# input1.net
KiCad netlist of a schematic drawn in Altium Designer
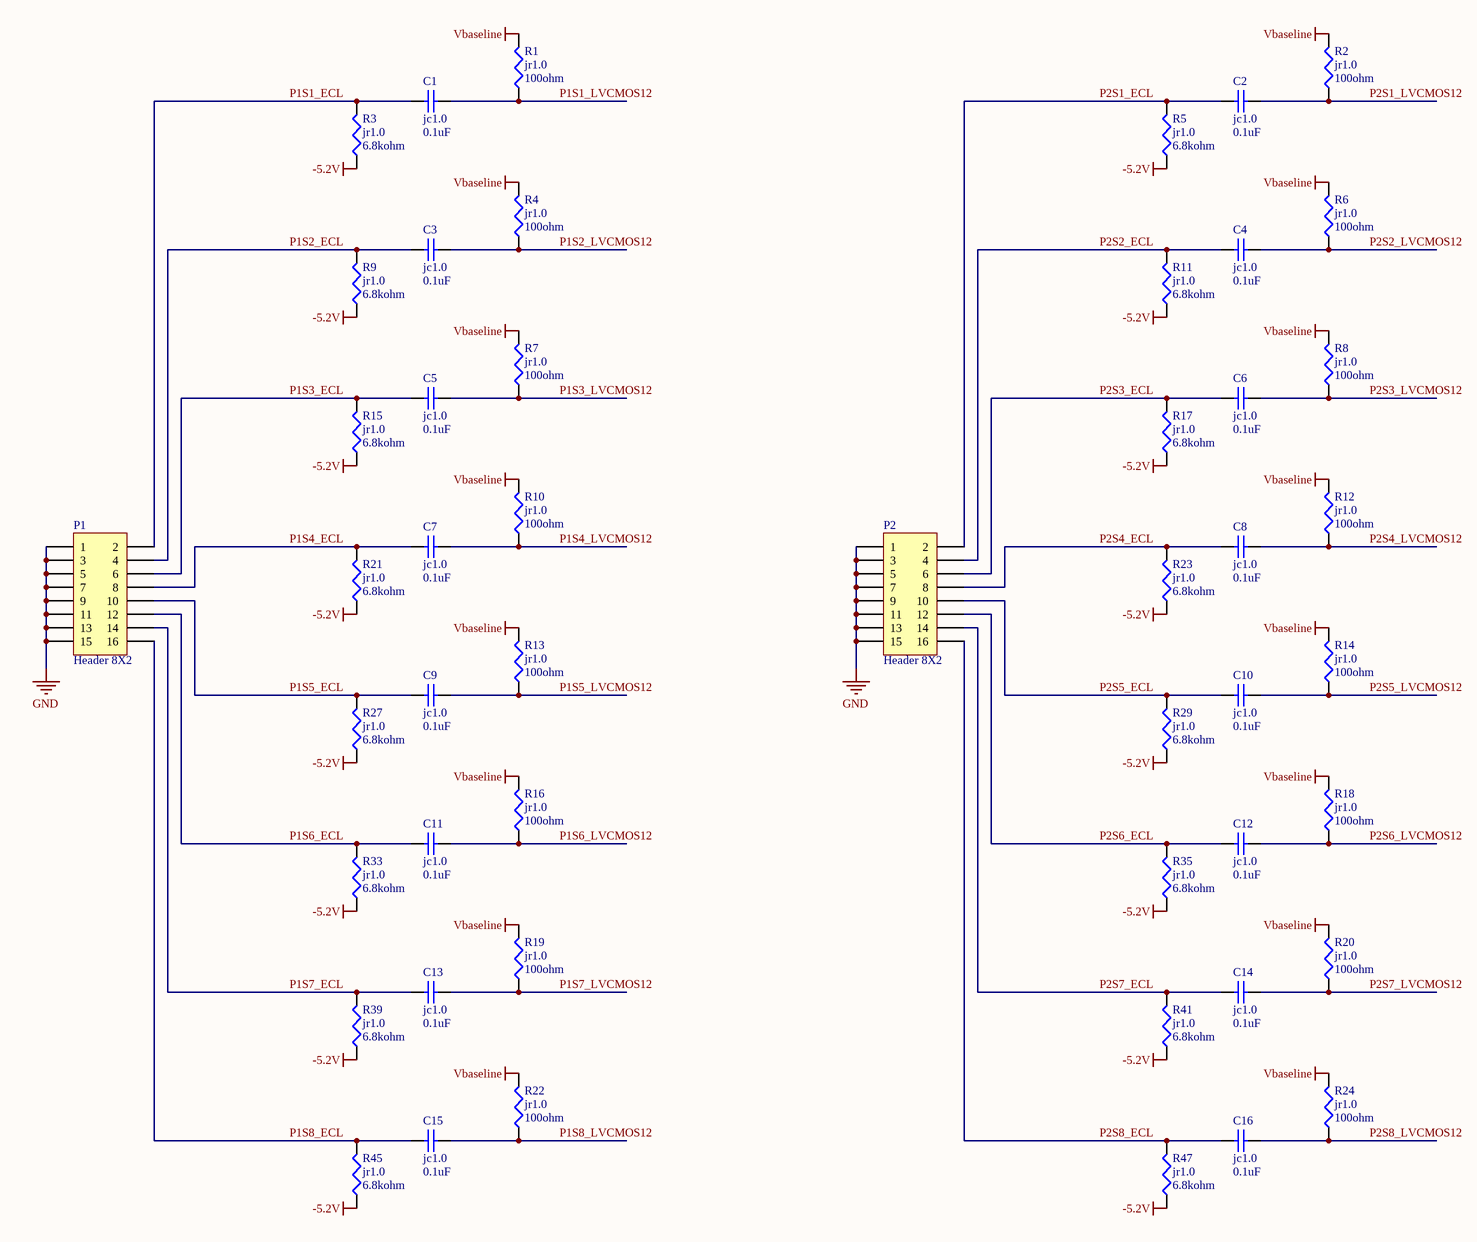
[diagram p0: input1.SchDoc]

(export (version "E")
  (design (tool "Eeschema 10.0.6"))
  (components
    (comp (ref "C1")
      (value "jc1.0")
      (footprint "0402")
      (description "Capacitor")
      (fields (field (name "ALTIUM_VALUE") "0.1uF") (field (name "PUBLISHER") "Altium Limited"))
      (libsource (lib "LIB01DXP2006SchLib") (part "Cap"))
    )
    (comp (ref "C2")
      (value "jc1.0")
      (footprint "0402")
      (description "Capacitor")
      (fields (field (name "ALTIUM_VALUE") "0.1uF") (field (name "PUBLISHER") "Altium Limited"))
      (libsource (lib "LIB01DXP2006SchLib") (part "Cap"))
    )
    (comp (ref "C3")
      (value "jc1.0")
      (footprint "0402")
      (description "Capacitor")
      (fields (field (name "ALTIUM_VALUE") "0.1uF") (field (name "PUBLISHER") "Altium Limited"))
      (libsource (lib "LIB01DXP2006SchLib") (part "Cap"))
    )
    (comp (ref "C4")
      (value "jc1.0")
      (footprint "0402")
      (description "Capacitor")
      (fields (field (name "ALTIUM_VALUE") "0.1uF") (field (name "PUBLISHER") "Altium Limited"))
      (libsource (lib "LIB01DXP2006SchLib") (part "Cap"))
    )
    (comp (ref "C5")
      (value "jc1.0")
      (footprint "0402")
      (description "Capacitor")
      (fields (field (name "ALTIUM_VALUE") "0.1uF") (field (name "PUBLISHER") "Altium Limited"))
      (libsource (lib "LIB01DXP2006SchLib") (part "Cap"))
    )
    (comp (ref "C6")
      (value "jc1.0")
      (footprint "0402")
      (description "Capacitor")
      (fields (field (name "ALTIUM_VALUE") "0.1uF") (field (name "PUBLISHER") "Altium Limited"))
      (libsource (lib "LIB01DXP2006SchLib") (part "Cap"))
    )
    (comp (ref "C7")
      (value "jc1.0")
      (footprint "0402")
      (description "Capacitor")
      (fields (field (name "ALTIUM_VALUE") "0.1uF") (field (name "PUBLISHER") "Altium Limited"))
      (libsource (lib "LIB01DXP2006SchLib") (part "Cap"))
    )
    (comp (ref "C8")
      (value "jc1.0")
      (footprint "0402")
      (description "Capacitor")
      (fields (field (name "ALTIUM_VALUE") "0.1uF") (field (name "PUBLISHER") "Altium Limited"))
      (libsource (lib "LIB01DXP2006SchLib") (part "Cap"))
    )
    (comp (ref "C9")
      (value "jc1.0")
      (footprint "0402")
      (description "Capacitor")
      (fields (field (name "ALTIUM_VALUE") "0.1uF") (field (name "PUBLISHER") "Altium Limited"))
      (libsource (lib "LIB01DXP2006SchLib") (part "Cap"))
    )
    (comp (ref "C10")
      (value "jc1.0")
      (footprint "0402")
      (description "Capacitor")
      (fields (field (name "ALTIUM_VALUE") "0.1uF") (field (name "PUBLISHER") "Altium Limited"))
      (libsource (lib "LIB01DXP2006SchLib") (part "Cap"))
    )
    (comp (ref "C11")
      (value "jc1.0")
      (footprint "0402")
      (description "Capacitor")
      (fields (field (name "ALTIUM_VALUE") "0.1uF") (field (name "PUBLISHER") "Altium Limited"))
      (libsource (lib "LIB01DXP2006SchLib") (part "Cap"))
    )
    (comp (ref "C12")
      (value "jc1.0")
      (footprint "0402")
      (description "Capacitor")
      (fields (field (name "ALTIUM_VALUE") "0.1uF") (field (name "PUBLISHER") "Altium Limited"))
      (libsource (lib "LIB01DXP2006SchLib") (part "Cap"))
    )
    (comp (ref "C13")
      (value "jc1.0")
      (footprint "0402")
      (description "Capacitor")
      (fields (field (name "ALTIUM_VALUE") "0.1uF") (field (name "PUBLISHER") "Altium Limited"))
      (libsource (lib "LIB01DXP2006SchLib") (part "Cap"))
    )
    (comp (ref "C14")
      (value "jc1.0")
      (footprint "0402")
      (description "Capacitor")
      (fields (field (name "ALTIUM_VALUE") "0.1uF") (field (name "PUBLISHER") "Altium Limited"))
      (libsource (lib "LIB01DXP2006SchLib") (part "Cap"))
    )
    (comp (ref "C15")
      (value "jc1.0")
      (footprint "0402")
      (description "Capacitor")
      (fields (field (name "ALTIUM_VALUE") "0.1uF") (field (name "PUBLISHER") "Altium Limited"))
      (libsource (lib "LIB01DXP2006SchLib") (part "Cap"))
    )
    (comp (ref "C16")
      (value "jc1.0")
      (footprint "0402")
      (description "Capacitor")
      (fields (field (name "ALTIUM_VALUE") "0.1uF") (field (name "PUBLISHER") "Altium Limited"))
      (libsource (lib "LIB01DXP2006SchLib") (part "Cap"))
    )
    (comp (ref "P1")
      (value "Header 8X2")
      (footprint "HDR2X8")
      (description "Header, 8-Pin, Dual row")
      (fields (field (name "PUBLISHER") "Altium Limited"))
      (libsource (lib "Miscellaneous Connectors") (part "Header 8X2"))
    )
    (comp (ref "P2")
      (value "Header 8X2")
      (footprint "HDR2X8")
      (description "Header, 8-Pin, Dual row")
      (fields (field (name "PUBLISHER") "Altium Limited"))
      (libsource (lib "Miscellaneous Connectors") (part "Header 8X2"))
    )
    (comp (ref "R1")
      (value "jr1.0")
      (footprint "0402")
      (description "Resistor")
      (fields (field (name "ALTIUM_VALUE") "100ohm") (field (name "PUBLISHER") "Altium Limited"))
      (libsource (lib "LIB01DXP2006SchLib") (part "Res"))
    )
    (comp (ref "R2")
      (value "jr1.0")
      (footprint "0402")
      (description "Resistor")
      (fields (field (name "ALTIUM_VALUE") "100ohm") (field (name "PUBLISHER") "Altium Limited"))
      (libsource (lib "LIB01DXP2006SchLib") (part "Res"))
    )
    (comp (ref "R3")
      (value "jr1.0")
      (footprint "0402")
      (description "Resistor")
      (fields (field (name "ALTIUM_VALUE") "6.8kohm") (field (name "PUBLISHER") "Altium Limited"))
      (libsource (lib "LIB01DXP2006SchLib") (part "Res"))
    )
    (comp (ref "R4")
      (value "jr1.0")
      (footprint "0402")
      (description "Resistor")
      (fields (field (name "ALTIUM_VALUE") "100ohm") (field (name "PUBLISHER") "Altium Limited"))
      (libsource (lib "LIB01DXP2006SchLib") (part "Res"))
    )
    (comp (ref "R5")
      (value "jr1.0")
      (footprint "0402")
      (description "Resistor")
      (fields (field (name "ALTIUM_VALUE") "6.8kohm") (field (name "PUBLISHER") "Altium Limited"))
      (libsource (lib "LIB01DXP2006SchLib") (part "Res"))
    )
    (comp (ref "R6")
      (value "jr1.0")
      (footprint "0402")
      (description "Resistor")
      (fields (field (name "ALTIUM_VALUE") "100ohm") (field (name "PUBLISHER") "Altium Limited"))
      (libsource (lib "LIB01DXP2006SchLib") (part "Res"))
    )
    (comp (ref "R7")
      (value "jr1.0")
      (footprint "0402")
      (description "Resistor")
      (fields (field (name "ALTIUM_VALUE") "100ohm") (field (name "PUBLISHER") "Altium Limited"))
      (libsource (lib "LIB01DXP2006SchLib") (part "Res"))
    )
    (comp (ref "R8")
      (value "jr1.0")
      (footprint "0402")
      (description "Resistor")
      (fields (field (name "ALTIUM_VALUE") "100ohm") (field (name "PUBLISHER") "Altium Limited"))
      (libsource (lib "LIB01DXP2006SchLib") (part "Res"))
    )
    (comp (ref "R9")
      (value "jr1.0")
      (footprint "0402")
      (description "Resistor")
      (fields (field (name "ALTIUM_VALUE") "6.8kohm") (field (name "PUBLISHER") "Altium Limited"))
      (libsource (lib "LIB01DXP2006SchLib") (part "Res"))
    )
    (comp (ref "R10")
      (value "jr1.0")
      (footprint "0402")
      (description "Resistor")
      (fields (field (name "ALTIUM_VALUE") "100ohm") (field (name "PUBLISHER") "Altium Limited"))
      (libsource (lib "LIB01DXP2006SchLib") (part "Res"))
    )
    (comp (ref "R11")
      (value "jr1.0")
      (footprint "0402")
      (description "Resistor")
      (fields (field (name "ALTIUM_VALUE") "6.8kohm") (field (name "PUBLISHER") "Altium Limited"))
      (libsource (lib "LIB01DXP2006SchLib") (part "Res"))
    )
    (comp (ref "R12")
      (value "jr1.0")
      (footprint "0402")
      (description "Resistor")
      (fields (field (name "ALTIUM_VALUE") "100ohm") (field (name "PUBLISHER") "Altium Limited"))
      (libsource (lib "LIB01DXP2006SchLib") (part "Res"))
    )
    (comp (ref "R13")
      (value "jr1.0")
      (footprint "0402")
      (description "Resistor")
      (fields (field (name "ALTIUM_VALUE") "100ohm") (field (name "PUBLISHER") "Altium Limited"))
      (libsource (lib "LIB01DXP2006SchLib") (part "Res"))
    )
    (comp (ref "R14")
      (value "jr1.0")
      (footprint "0402")
      (description "Resistor")
      (fields (field (name "ALTIUM_VALUE") "100ohm") (field (name "PUBLISHER") "Altium Limited"))
      (libsource (lib "LIB01DXP2006SchLib") (part "Res"))
    )
    (comp (ref "R15")
      (value "jr1.0")
      (footprint "0402")
      (description "Resistor")
      (fields (field (name "ALTIUM_VALUE") "6.8kohm") (field (name "PUBLISHER") "Altium Limited"))
      (libsource (lib "LIB01DXP2006SchLib") (part "Res"))
    )
    (comp (ref "R16")
      (value "jr1.0")
      (footprint "0402")
      (description "Resistor")
      (fields (field (name "ALTIUM_VALUE") "100ohm") (field (name "PUBLISHER") "Altium Limited"))
      (libsource (lib "LIB01DXP2006SchLib") (part "Res"))
    )
    (comp (ref "R17")
      (value "jr1.0")
      (footprint "0402")
      (description "Resistor")
      (fields (field (name "ALTIUM_VALUE") "6.8kohm") (field (name "PUBLISHER") "Altium Limited"))
      (libsource (lib "LIB01DXP2006SchLib") (part "Res"))
    )
    (comp (ref "R18")
      (value "jr1.0")
      (footprint "0402")
      (description "Resistor")
      (fields (field (name "ALTIUM_VALUE") "100ohm") (field (name "PUBLISHER") "Altium Limited"))
      (libsource (lib "LIB01DXP2006SchLib") (part "Res"))
    )
    (comp (ref "R19")
      (value "jr1.0")
      (footprint "0402")
      (description "Resistor")
      (fields (field (name "ALTIUM_VALUE") "100ohm") (field (name "PUBLISHER") "Altium Limited"))
      (libsource (lib "LIB01DXP2006SchLib") (part "Res"))
    )
    (comp (ref "R20")
      (value "jr1.0")
      (footprint "0402")
      (description "Resistor")
      (fields (field (name "ALTIUM_VALUE") "100ohm") (field (name "PUBLISHER") "Altium Limited"))
      (libsource (lib "LIB01DXP2006SchLib") (part "Res"))
    )
    (comp (ref "R21")
      (value "jr1.0")
      (footprint "0402")
      (description "Resistor")
      (fields (field (name "ALTIUM_VALUE") "6.8kohm") (field (name "PUBLISHER") "Altium Limited"))
      (libsource (lib "LIB01DXP2006SchLib") (part "Res"))
    )
    (comp (ref "R22")
      (value "jr1.0")
      (footprint "0402")
      (description "Resistor")
      (fields (field (name "ALTIUM_VALUE") "100ohm") (field (name "PUBLISHER") "Altium Limited"))
      (libsource (lib "LIB01DXP2006SchLib") (part "Res"))
    )
    (comp (ref "R23")
      (value "jr1.0")
      (footprint "0402")
      (description "Resistor")
      (fields (field (name "ALTIUM_VALUE") "6.8kohm") (field (name "PUBLISHER") "Altium Limited"))
      (libsource (lib "LIB01DXP2006SchLib") (part "Res"))
    )
    (comp (ref "R24")
      (value "jr1.0")
      (footprint "0402")
      (description "Resistor")
      (fields (field (name "ALTIUM_VALUE") "100ohm") (field (name "PUBLISHER") "Altium Limited"))
      (libsource (lib "LIB01DXP2006SchLib") (part "Res"))
    )
    (comp (ref "R27")
      (value "jr1.0")
      (footprint "0402")
      (description "Resistor")
      (fields (field (name "ALTIUM_VALUE") "6.8kohm") (field (name "PUBLISHER") "Altium Limited"))
      (libsource (lib "LIB01DXP2006SchLib") (part "Res"))
    )
    (comp (ref "R29")
      (value "jr1.0")
      (footprint "0402")
      (description "Resistor")
      (fields (field (name "ALTIUM_VALUE") "6.8kohm") (field (name "PUBLISHER") "Altium Limited"))
      (libsource (lib "LIB01DXP2006SchLib") (part "Res"))
    )
    (comp (ref "R33")
      (value "jr1.0")
      (footprint "0402")
      (description "Resistor")
      (fields (field (name "ALTIUM_VALUE") "6.8kohm") (field (name "PUBLISHER") "Altium Limited"))
      (libsource (lib "LIB01DXP2006SchLib") (part "Res"))
    )
    (comp (ref "R35")
      (value "jr1.0")
      (footprint "0402")
      (description "Resistor")
      (fields (field (name "ALTIUM_VALUE") "6.8kohm") (field (name "PUBLISHER") "Altium Limited"))
      (libsource (lib "LIB01DXP2006SchLib") (part "Res"))
    )
    (comp (ref "R39")
      (value "jr1.0")
      (footprint "0402")
      (description "Resistor")
      (fields (field (name "ALTIUM_VALUE") "6.8kohm") (field (name "PUBLISHER") "Altium Limited"))
      (libsource (lib "LIB01DXP2006SchLib") (part "Res"))
    )
    (comp (ref "R41")
      (value "jr1.0")
      (footprint "0402")
      (description "Resistor")
      (fields (field (name "ALTIUM_VALUE") "6.8kohm") (field (name "PUBLISHER") "Altium Limited"))
      (libsource (lib "LIB01DXP2006SchLib") (part "Res"))
    )
    (comp (ref "R45")
      (value "jr1.0")
      (footprint "0402")
      (description "Resistor")
      (fields (field (name "ALTIUM_VALUE") "6.8kohm") (field (name "PUBLISHER") "Altium Limited"))
      (libsource (lib "LIB01DXP2006SchLib") (part "Res"))
    )
    (comp (ref "R47")
      (value "jr1.0")
      (footprint "0402")
      (description "Resistor")
      (fields (field (name "ALTIUM_VALUE") "6.8kohm") (field (name "PUBLISHER") "Altium Limited"))
      (libsource (lib "LIB01DXP2006SchLib") (part "Res"))
    )
  )
  (nets
    (net (code "1") (name "-5.2V") (class "Default")
      (node (ref "R11") (pin "1") (pinfunction "1_1") (pintype "passive"))
      (node (ref "R15") (pin "1") (pinfunction "1_1") (pintype "passive"))
      (node (ref "R17") (pin "1") (pinfunction "1_1") (pintype "passive"))
      (node (ref "R21") (pin "1") (pinfunction "1_1") (pintype "passive"))
      (node (ref "R23") (pin "1") (pinfunction "1_1") (pintype "passive"))
      (node (ref "R27") (pin "1") (pinfunction "1_1") (pintype "passive"))
      (node (ref "R29") (pin "1") (pinfunction "1_1") (pintype "passive"))
      (node (ref "R3") (pin "1") (pinfunction "1_1") (pintype "passive"))
      (node (ref "R33") (pin "1") (pinfunction "1_1") (pintype "passive"))
      (node (ref "R35") (pin "1") (pinfunction "1_1") (pintype "passive"))
      (node (ref "R39") (pin "1") (pinfunction "1_1") (pintype "passive"))
      (node (ref "R41") (pin "1") (pinfunction "1_1") (pintype "passive"))
      (node (ref "R45") (pin "1") (pinfunction "1_1") (pintype "passive"))
      (node (ref "R47") (pin "1") (pinfunction "1_1") (pintype "passive"))
      (node (ref "R5") (pin "1") (pinfunction "1_1") (pintype "passive"))
      (node (ref "R9") (pin "1") (pinfunction "1_1") (pintype "passive"))
    )
    (net (code "2") (name "/P1S1_ECL") (class "Default")
      (node (ref "C1") (pin "1") (pinfunction "1_1") (pintype "passive"))
      (node (ref "P1") (pin "2") (pinfunction "2_2") (pintype "passive"))
      (node (ref "R3") (pin "2") (pinfunction "2_2") (pintype "passive"))
    )
    (net (code "3") (name "/P1S1_LVCMOS12") (class "Default")
      (node (ref "C1") (pin "2") (pinfunction "2_2") (pintype "passive"))
      (node (ref "R1") (pin "1") (pinfunction "1_1") (pintype "passive"))
    )
    (net (code "4") (name "/P1S2_ECL") (class "Default")
      (node (ref "C3") (pin "1") (pinfunction "1_1") (pintype "passive"))
      (node (ref "P1") (pin "4") (pinfunction "4_4") (pintype "passive"))
      (node (ref "R9") (pin "2") (pinfunction "2_2") (pintype "passive"))
    )
    (net (code "5") (name "/P1S2_LVCMOS12") (class "Default")
      (node (ref "C3") (pin "2") (pinfunction "2_2") (pintype "passive"))
      (node (ref "R4") (pin "1") (pinfunction "1_1") (pintype "passive"))
    )
    (net (code "6") (name "/P1S3_ECL") (class "Default")
      (node (ref "C5") (pin "1") (pinfunction "1_1") (pintype "passive"))
      (node (ref "P1") (pin "6") (pinfunction "6_6") (pintype "passive"))
      (node (ref "R15") (pin "2") (pinfunction "2_2") (pintype "passive"))
    )
    (net (code "7") (name "/P1S3_LVCMOS12") (class "Default")
      (node (ref "C5") (pin "2") (pinfunction "2_2") (pintype "passive"))
      (node (ref "R7") (pin "1") (pinfunction "1_1") (pintype "passive"))
    )
    (net (code "8") (name "/P1S4_ECL") (class "Default")
      (node (ref "C7") (pin "1") (pinfunction "1_1") (pintype "passive"))
      (node (ref "P1") (pin "8") (pinfunction "8_8") (pintype "passive"))
      (node (ref "R21") (pin "2") (pinfunction "2_2") (pintype "passive"))
    )
    (net (code "9") (name "/P1S4_LVCMOS12") (class "Default")
      (node (ref "C7") (pin "2") (pinfunction "2_2") (pintype "passive"))
      (node (ref "R10") (pin "1") (pinfunction "1_1") (pintype "passive"))
    )
    (net (code "10") (name "/P1S5_ECL") (class "Default")
      (node (ref "C9") (pin "1") (pinfunction "1_1") (pintype "passive"))
      (node (ref "P1") (pin "10") (pinfunction "10_10") (pintype "passive"))
      (node (ref "R27") (pin "2") (pinfunction "2_2") (pintype "passive"))
    )
    (net (code "11") (name "/P1S5_LVCMOS12") (class "Default")
      (node (ref "C9") (pin "2") (pinfunction "2_2") (pintype "passive"))
      (node (ref "R13") (pin "1") (pinfunction "1_1") (pintype "passive"))
    )
    (net (code "12") (name "/P1S6_ECL") (class "Default")
      (node (ref "C11") (pin "1") (pinfunction "1_1") (pintype "passive"))
      (node (ref "P1") (pin "12") (pinfunction "12_12") (pintype "passive"))
      (node (ref "R33") (pin "2") (pinfunction "2_2") (pintype "passive"))
    )
    (net (code "13") (name "/P1S6_LVCMOS12") (class "Default")
      (node (ref "C11") (pin "2") (pinfunction "2_2") (pintype "passive"))
      (node (ref "R16") (pin "1") (pinfunction "1_1") (pintype "passive"))
    )
    (net (code "14") (name "/P1S7_ECL") (class "Default")
      (node (ref "C13") (pin "1") (pinfunction "1_1") (pintype "passive"))
      (node (ref "P1") (pin "14") (pinfunction "14_14") (pintype "passive"))
      (node (ref "R39") (pin "2") (pinfunction "2_2") (pintype "passive"))
    )
    (net (code "15") (name "/P1S7_LVCMOS12") (class "Default")
      (node (ref "C13") (pin "2") (pinfunction "2_2") (pintype "passive"))
      (node (ref "R19") (pin "1") (pinfunction "1_1") (pintype "passive"))
    )
    (net (code "16") (name "/P1S8_ECL") (class "Default")
      (node (ref "C15") (pin "1") (pinfunction "1_1") (pintype "passive"))
      (node (ref "P1") (pin "16") (pinfunction "16_16") (pintype "passive"))
      (node (ref "R45") (pin "2") (pinfunction "2_2") (pintype "passive"))
    )
    (net (code "17") (name "/P1S8_LVCMOS12") (class "Default")
      (node (ref "C15") (pin "2") (pinfunction "2_2") (pintype "passive"))
      (node (ref "R22") (pin "1") (pinfunction "1_1") (pintype "passive"))
    )
    (net (code "18") (name "/P2S1_ECL") (class "Default")
      (node (ref "C2") (pin "1") (pinfunction "1_1") (pintype "passive"))
      (node (ref "P2") (pin "2") (pinfunction "2_2") (pintype "passive"))
      (node (ref "R5") (pin "2") (pinfunction "2_2") (pintype "passive"))
    )
    (net (code "19") (name "/P2S1_LVCMOS12") (class "Default")
      (node (ref "C2") (pin "2") (pinfunction "2_2") (pintype "passive"))
      (node (ref "R2") (pin "1") (pinfunction "1_1") (pintype "passive"))
    )
    (net (code "20") (name "/P2S2_ECL") (class "Default")
      (node (ref "C4") (pin "1") (pinfunction "1_1") (pintype "passive"))
      (node (ref "P2") (pin "4") (pinfunction "4_4") (pintype "passive"))
      (node (ref "R11") (pin "2") (pinfunction "2_2") (pintype "passive"))
    )
    (net (code "21") (name "/P2S2_LVCMOS12") (class "Default")
      (node (ref "C4") (pin "2") (pinfunction "2_2") (pintype "passive"))
      (node (ref "R6") (pin "1") (pinfunction "1_1") (pintype "passive"))
    )
    (net (code "22") (name "/P2S3_ECL") (class "Default")
      (node (ref "C6") (pin "1") (pinfunction "1_1") (pintype "passive"))
      (node (ref "P2") (pin "6") (pinfunction "6_6") (pintype "passive"))
      (node (ref "R17") (pin "2") (pinfunction "2_2") (pintype "passive"))
    )
    (net (code "23") (name "/P2S3_LVCMOS12") (class "Default")
      (node (ref "C6") (pin "2") (pinfunction "2_2") (pintype "passive"))
      (node (ref "R8") (pin "1") (pinfunction "1_1") (pintype "passive"))
    )
    (net (code "24") (name "/P2S4_ECL") (class "Default")
      (node (ref "C8") (pin "1") (pinfunction "1_1") (pintype "passive"))
      (node (ref "P2") (pin "8") (pinfunction "8_8") (pintype "passive"))
      (node (ref "R23") (pin "2") (pinfunction "2_2") (pintype "passive"))
    )
    (net (code "25") (name "/P2S4_LVCMOS12") (class "Default")
      (node (ref "C8") (pin "2") (pinfunction "2_2") (pintype "passive"))
      (node (ref "R12") (pin "1") (pinfunction "1_1") (pintype "passive"))
    )
    (net (code "26") (name "/P2S5_ECL") (class "Default")
      (node (ref "C10") (pin "1") (pinfunction "1_1") (pintype "passive"))
      (node (ref "P2") (pin "10") (pinfunction "10_10") (pintype "passive"))
      (node (ref "R29") (pin "2") (pinfunction "2_2") (pintype "passive"))
    )
    (net (code "27") (name "/P2S5_LVCMOS12") (class "Default")
      (node (ref "C10") (pin "2") (pinfunction "2_2") (pintype "passive"))
      (node (ref "R14") (pin "1") (pinfunction "1_1") (pintype "passive"))
    )
    (net (code "28") (name "/P2S6_ECL") (class "Default")
      (node (ref "C12") (pin "1") (pinfunction "1_1") (pintype "passive"))
      (node (ref "P2") (pin "12") (pinfunction "12_12") (pintype "passive"))
      (node (ref "R35") (pin "2") (pinfunction "2_2") (pintype "passive"))
    )
    (net (code "29") (name "/P2S6_LVCMOS12") (class "Default")
      (node (ref "C12") (pin "2") (pinfunction "2_2") (pintype "passive"))
      (node (ref "R18") (pin "1") (pinfunction "1_1") (pintype "passive"))
    )
    (net (code "30") (name "/P2S7_ECL") (class "Default")
      (node (ref "C14") (pin "1") (pinfunction "1_1") (pintype "passive"))
      (node (ref "P2") (pin "14") (pinfunction "14_14") (pintype "passive"))
      (node (ref "R41") (pin "2") (pinfunction "2_2") (pintype "passive"))
    )
    (net (code "31") (name "/P2S7_LVCMOS12") (class "Default")
      (node (ref "C14") (pin "2") (pinfunction "2_2") (pintype "passive"))
      (node (ref "R20") (pin "1") (pinfunction "1_1") (pintype "passive"))
    )
    (net (code "32") (name "/P2S8_ECL") (class "Default")
      (node (ref "C16") (pin "1") (pinfunction "1_1") (pintype "passive"))
      (node (ref "P2") (pin "16") (pinfunction "16_16") (pintype "passive"))
      (node (ref "R47") (pin "2") (pinfunction "2_2") (pintype "passive"))
    )
    (net (code "33") (name "/P2S8_LVCMOS12") (class "Default")
      (node (ref "C16") (pin "2") (pinfunction "2_2") (pintype "passive"))
      (node (ref "R24") (pin "1") (pinfunction "1_1") (pintype "passive"))
    )
    (net (code "34") (name "GND") (class "Default")
      (node (ref "P1") (pin "1") (pinfunction "1_1") (pintype "passive"))
      (node (ref "P1") (pin "11") (pinfunction "11_11") (pintype "passive"))
      (node (ref "P1") (pin "13") (pinfunction "13_13") (pintype "passive"))
      (node (ref "P1") (pin "15") (pinfunction "15_15") (pintype "passive"))
      (node (ref "P1") (pin "3") (pinfunction "3_3") (pintype "passive"))
      (node (ref "P1") (pin "5") (pinfunction "5_5") (pintype "passive"))
      (node (ref "P1") (pin "7") (pinfunction "7_7") (pintype "passive"))
      (node (ref "P1") (pin "9") (pinfunction "9_9") (pintype "passive"))
      (node (ref "P2") (pin "1") (pinfunction "1_1") (pintype "passive"))
      (node (ref "P2") (pin "11") (pinfunction "11_11") (pintype "passive"))
      (node (ref "P2") (pin "13") (pinfunction "13_13") (pintype "passive"))
      (node (ref "P2") (pin "15") (pinfunction "15_15") (pintype "passive"))
      (node (ref "P2") (pin "3") (pinfunction "3_3") (pintype "passive"))
      (node (ref "P2") (pin "5") (pinfunction "5_5") (pintype "passive"))
      (node (ref "P2") (pin "7") (pinfunction "7_7") (pintype "passive"))
      (node (ref "P2") (pin "9") (pinfunction "9_9") (pintype "passive"))
    )
    (net (code "35") (name "Vbaseline") (class "Default")
      (node (ref "R1") (pin "2") (pinfunction "2_2") (pintype "passive"))
      (node (ref "R10") (pin "2") (pinfunction "2_2") (pintype "passive"))
      (node (ref "R12") (pin "2") (pinfunction "2_2") (pintype "passive"))
      (node (ref "R13") (pin "2") (pinfunction "2_2") (pintype "passive"))
      (node (ref "R14") (pin "2") (pinfunction "2_2") (pintype "passive"))
      (node (ref "R16") (pin "2") (pinfunction "2_2") (pintype "passive"))
      (node (ref "R18") (pin "2") (pinfunction "2_2") (pintype "passive"))
      (node (ref "R19") (pin "2") (pinfunction "2_2") (pintype "passive"))
      (node (ref "R2") (pin "2") (pinfunction "2_2") (pintype "passive"))
      (node (ref "R20") (pin "2") (pinfunction "2_2") (pintype "passive"))
      (node (ref "R22") (pin "2") (pinfunction "2_2") (pintype "passive"))
      (node (ref "R24") (pin "2") (pinfunction "2_2") (pintype "passive"))
      (node (ref "R4") (pin "2") (pinfunction "2_2") (pintype "passive"))
      (node (ref "R6") (pin "2") (pinfunction "2_2") (pintype "passive"))
      (node (ref "R7") (pin "2") (pinfunction "2_2") (pintype "passive"))
      (node (ref "R8") (pin "2") (pinfunction "2_2") (pintype "passive"))
    )
  )
)
